# Power_Board_Testing_Interface.net
KiCad netlist of a schematic drawn in EAGLE
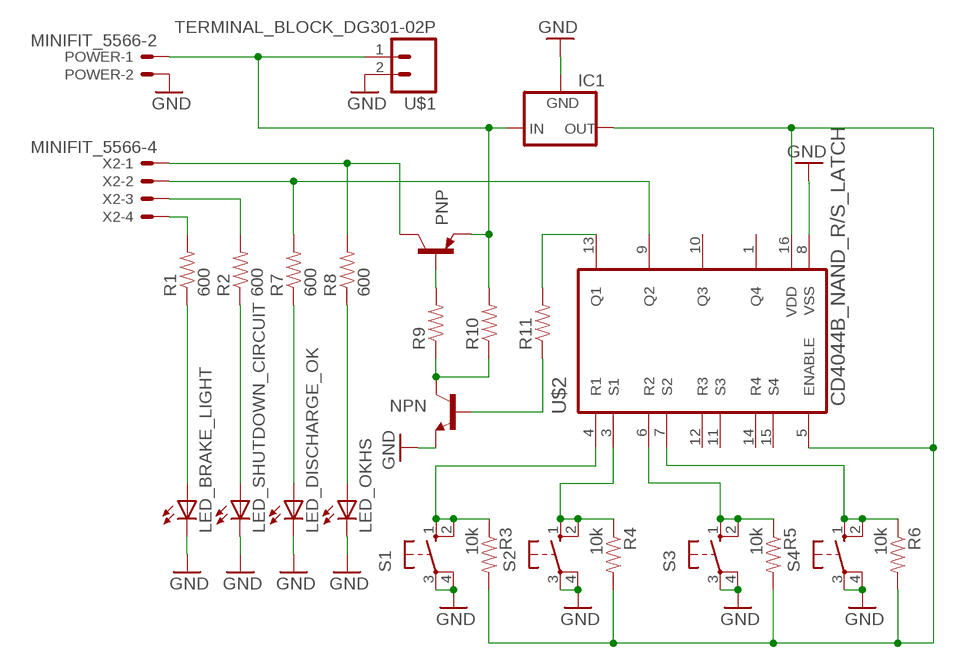
[diagram p0: schematic, sheet 1]

(export (version "E")
  (design (tool "Eeschema 10.0.6"))
  (components
    (comp (ref "IC1")
      (value "5V_REGULATOR_L7805SWITCHING")
      (footprint "eagle-import:TO-220")
      (libsource (lib "eagle-import") (part "5V_REGULATOR_L7805SWITCHING"))
    )
    (comp (ref "LED_BRAKE_LIGHT")
      (value "LED-5MM")
      (footprint "eagle-import:LED-5MM")
      (libsource (lib "eagle-import") (part "LED-5MM"))
    )
    (comp (ref "LED_DISCHARGE_OK")
      (value "LED-5MM")
      (footprint "eagle-import:LED-5MM")
      (libsource (lib "eagle-import") (part "LED-5MM"))
    )
    (comp (ref "LED_OKHS")
      (value "LED-5MM")
      (footprint "eagle-import:LED-5MM")
      (libsource (lib "eagle-import") (part "LED-5MM"))
    )
    (comp (ref "LED_SHUTDOWN_CIRCUIT")
      (value "LED-5MM")
      (footprint "eagle-import:LED-5MM")
      (libsource (lib "eagle-import") (part "LED-5MM"))
    )
    (comp (ref "NPN")
      (value "BJT_NPNTIP120")
      (footprint "eagle-import:TO-220")
      (libsource (lib "eagle-import") (part "BJT_NPNTIP120"))
    )
    (comp (ref "PNP")
      (value "BJT_PNP")
      (footprint "eagle-import:TO-220")
      (libsource (lib "eagle-import") (part "BJT_PNP"))
    )
    (comp (ref "POWER")
      (value "MINIFIT_5566-2")
      (footprint "eagle-import:MINIFIT_5566-2")
      (libsource (lib "eagle-import") (part "MINIFIT_5566-2"))
    )
    (comp (ref "R1")
      (value "600")
      (footprint "eagle-import:AXIAL-0.3EZ")
      (libsource (lib "eagle-import") (part "RESISTOREZ"))
    )
    (comp (ref "R2")
      (value "600")
      (footprint "eagle-import:AXIAL-0.3EZ")
      (libsource (lib "eagle-import") (part "RESISTOREZ"))
    )
    (comp (ref "R3")
      (value "10k")
      (footprint "eagle-import:AXIAL-0.3EZ")
      (libsource (lib "eagle-import") (part "RESISTOREZ"))
    )
    (comp (ref "R4")
      (value "10k")
      (footprint "eagle-import:AXIAL-0.3EZ")
      (libsource (lib "eagle-import") (part "RESISTOREZ"))
    )
    (comp (ref "R5")
      (value "10k")
      (footprint "eagle-import:AXIAL-0.3EZ")
      (libsource (lib "eagle-import") (part "RESISTOREZ"))
    )
    (comp (ref "R6")
      (value "10k")
      (footprint "eagle-import:AXIAL-0.3EZ")
      (libsource (lib "eagle-import") (part "RESISTOREZ"))
    )
    (comp (ref "R7")
      (value "600")
      (footprint "eagle-import:AXIAL-0.3EZ")
      (libsource (lib "eagle-import") (part "RESISTOREZ"))
    )
    (comp (ref "R8")
      (value "600")
      (footprint "eagle-import:AXIAL-0.3EZ")
      (libsource (lib "eagle-import") (part "RESISTOREZ"))
    )
    (comp (ref "R9")
      (value "RESISTOREZ")
      (footprint "eagle-import:AXIAL-0.3EZ")
      (libsource (lib "eagle-import") (part "RESISTOREZ"))
    )
    (comp (ref "R10")
      (value "RESISTOREZ")
      (footprint "eagle-import:AXIAL-0.3EZ")
      (libsource (lib "eagle-import") (part "RESISTOREZ"))
    )
    (comp (ref "R11")
      (value "RESISTOREZ")
      (footprint "eagle-import:AXIAL-0.3EZ")
      (libsource (lib "eagle-import") (part "RESISTOREZ"))
    )
    (comp (ref "S1")
      (value "BTN_10-XX")
      (footprint "eagle-import:B3F-10XX")
      (fields (field (name "MPN") "B3F-1000"))
      (libsource (lib "eagle-import") (part "BTN_10-XX"))
    )
    (comp (ref "S2")
      (value "BTN_10-XX")
      (footprint "eagle-import:B3F-10XX")
      (fields (field (name "MPN") "B3F-1000"))
      (libsource (lib "eagle-import") (part "BTN_10-XX"))
    )
    (comp (ref "S3")
      (value "BTN_10-XX")
      (footprint "eagle-import:B3F-10XX")
      (fields (field (name "MPN") "B3F-1000"))
      (libsource (lib "eagle-import") (part "BTN_10-XX"))
    )
    (comp (ref "S4")
      (value "BTN_10-XX")
      (footprint "eagle-import:B3F-10XX")
      (fields (field (name "MPN") "B3F-1000"))
      (libsource (lib "eagle-import") (part "BTN_10-XX"))
    )
    (comp (ref "U$1")
      (value "TERMINAL_BLOCK_DG301-02P")
      (footprint "eagle-import:DG301-02P")
      (libsource (lib "eagle-import") (part "TERMINAL_BLOCK_DG301-02P"))
    )
    (comp (ref "U$2")
      (value "CD4044B_NAND_R/S_LATCH")
      (footprint "eagle-import:DIL16")
      (libsource (lib "eagle-import") (part "CD4044B_NAND_R/S_LATCH"))
    )
    (comp (ref "X2")
      (value "MINIFIT_5566-4")
      (footprint "eagle-import:MINIFIT_5566-4")
      (libsource (lib "eagle-import") (part "MINIFIT_5566-4"))
    )
  )
  (nets
    (net (code "1") (name "/R3") (class "Default")
      (node (ref "U$2") (pin "12") (pinfunction "R3_12") (pintype "power_in"))
    )
    (net (code "2") (name "GND") (class "Default")
      (node (ref "IC1") (pin "2") (pinfunction "GND_2") (pintype "input"))
      (node (ref "LED_BRAKE_LIGHT") (pin "K") (pinfunction "C_K") (pintype "passive"))
      (node (ref "LED_DISCHARGE_OK") (pin "K") (pinfunction "C_K") (pintype "passive"))
      (node (ref "LED_OKHS") (pin "K") (pinfunction "C_K") (pintype "passive"))
      (node (ref "LED_SHUTDOWN_CIRCUIT") (pin "K") (pinfunction "C_K") (pintype "passive"))
      (node (ref "NPN") (pin "3") (pinfunction "EMITTER_3") (pintype "passive"))
      (node (ref "POWER") (pin "2") (pinfunction "S_2") (pintype "passive"))
      (node (ref "S1") (pin "3") (pinfunction "P_3") (pintype "passive"))
      (node (ref "S1") (pin "4") (pinfunction "P1_4") (pintype "passive"))
      (node (ref "S2") (pin "3") (pinfunction "P_3") (pintype "passive"))
      (node (ref "S2") (pin "4") (pinfunction "P1_4") (pintype "passive"))
      (node (ref "S3") (pin "3") (pinfunction "P_3") (pintype "passive"))
      (node (ref "S3") (pin "4") (pinfunction "P1_4") (pintype "passive"))
      (node (ref "S4") (pin "3") (pinfunction "P_3") (pintype "passive"))
      (node (ref "S4") (pin "4") (pinfunction "P1_4") (pintype "passive"))
      (node (ref "U$1") (pin "2") (pinfunction "2_2") (pintype "passive"))
      (node (ref "U$2") (pin "8") (pinfunction "VSS_8") (pintype "bidirectional"))
    )
    (net (code "3") (name "Net-(IC1-IN)") (class "Default")
      (node (ref "IC1") (pin "1") (pinfunction "IN_1") (pintype "input"))
      (node (ref "PNP") (pin "3") (pinfunction "E_3") (pintype "passive"))
      (node (ref "POWER") (pin "1") (pinfunction "S_1") (pintype "passive"))
      (node (ref "R10") (pin "P$2") (pinfunction "2_P$2") (pintype "passive"))
      (node (ref "U$1") (pin "1") (pinfunction "1_1") (pintype "passive"))
    )
    (net (code "4") (name "Net-(IC1-OUT)") (class "Default")
      (node (ref "IC1") (pin "3") (pinfunction "OUT_3") (pintype "output"))
      (node (ref "R3") (pin "P$2") (pinfunction "2_P$2") (pintype "passive"))
      (node (ref "R4") (pin "P$2") (pinfunction "2_P$2") (pintype "passive"))
      (node (ref "R5") (pin "P$2") (pinfunction "2_P$2") (pintype "passive"))
      (node (ref "R6") (pin "P$2") (pinfunction "2_P$2") (pintype "passive"))
      (node (ref "U$2") (pin "16") (pinfunction "VDD_16") (pintype "bidirectional"))
      (node (ref "U$2") (pin "5") (pinfunction "ENABLE_5") (pintype "passive"))
    )
    (net (code "5") (name "Net-(NPN-BASE)") (class "Default")
      (node (ref "NPN") (pin "1") (pinfunction "BASE_1") (pintype "passive"))
      (node (ref "R11") (pin "P$1") (pinfunction "1_P$1") (pintype "passive"))
    )
    (net (code "6") (name "Net-(NPN-COLLECTOR)") (class "Default")
      (node (ref "NPN") (pin "2") (pinfunction "COLLECTOR_2") (pintype "passive"))
      (node (ref "R10") (pin "P$1") (pinfunction "1_P$1") (pintype "passive"))
      (node (ref "R9") (pin "P$1") (pinfunction "1_P$1") (pintype "passive"))
    )
    (net (code "7") (name "Net-(PNP-B)") (class "Default")
      (node (ref "PNP") (pin "1") (pinfunction "B_1") (pintype "passive"))
      (node (ref "R9") (pin "P$2") (pinfunction "2_P$2") (pintype "passive"))
    )
    (net (code "8") (name "Net-(PNP-C)") (class "Default")
      (node (ref "PNP") (pin "2") (pinfunction "C_2") (pintype "passive"))
      (node (ref "R8") (pin "P$2") (pinfunction "2_P$2") (pintype "passive"))
      (node (ref "X2") (pin "1") (pinfunction "S_1") (pintype "passive"))
    )
    (net (code "9") (name "Net-(R1-1)") (class "Default")
      (node (ref "LED_BRAKE_LIGHT") (pin "A") (pinfunction "A_A") (pintype "passive"))
      (node (ref "R1") (pin "P$1") (pinfunction "1_P$1") (pintype "passive"))
    )
    (net (code "10") (name "Net-(R1-2)") (class "Default")
      (node (ref "R1") (pin "P$2") (pinfunction "2_P$2") (pintype "passive"))
      (node (ref "X2") (pin "4") (pinfunction "S_4") (pintype "passive"))
    )
    (net (code "11") (name "Net-(R2-1)") (class "Default")
      (node (ref "LED_SHUTDOWN_CIRCUIT") (pin "A") (pinfunction "A_A") (pintype "passive"))
      (node (ref "R2") (pin "P$1") (pinfunction "1_P$1") (pintype "passive"))
    )
    (net (code "12") (name "Net-(R2-2)") (class "Default")
      (node (ref "R2") (pin "P$2") (pinfunction "2_P$2") (pintype "passive"))
      (node (ref "X2") (pin "3") (pinfunction "S_3") (pintype "passive"))
    )
    (net (code "13") (name "Net-(R3-1)") (class "Default")
      (node (ref "R3") (pin "P$1") (pinfunction "1_P$1") (pintype "passive"))
      (node (ref "S1") (pin "1") (pinfunction "S_1") (pintype "passive"))
      (node (ref "S1") (pin "2") (pinfunction "S1_2") (pintype "passive"))
      (node (ref "U$2") (pin "4") (pinfunction "R1_4") (pintype "power_in"))
    )
    (net (code "14") (name "Net-(R4-1)") (class "Default")
      (node (ref "R4") (pin "P$1") (pinfunction "1_P$1") (pintype "passive"))
      (node (ref "S2") (pin "1") (pinfunction "S_1") (pintype "passive"))
      (node (ref "S2") (pin "2") (pinfunction "S1_2") (pintype "passive"))
      (node (ref "U$2") (pin "3") (pinfunction "S1_3") (pintype "input"))
    )
    (net (code "15") (name "Net-(R5-1)") (class "Default")
      (node (ref "R5") (pin "P$1") (pinfunction "1_P$1") (pintype "passive"))
      (node (ref "S3") (pin "1") (pinfunction "S_1") (pintype "passive"))
      (node (ref "S3") (pin "2") (pinfunction "S1_2") (pintype "passive"))
      (node (ref "U$2") (pin "6") (pinfunction "R2_6") (pintype "input"))
    )
    (net (code "16") (name "Net-(R6-1)") (class "Default")
      (node (ref "R6") (pin "P$1") (pinfunction "1_P$1") (pintype "passive"))
      (node (ref "S4") (pin "1") (pinfunction "S_1") (pintype "passive"))
      (node (ref "S4") (pin "2") (pinfunction "S1_2") (pintype "passive"))
      (node (ref "U$2") (pin "7") (pinfunction "S2_7") (pintype "input"))
    )
    (net (code "17") (name "Net-(R7-1)") (class "Default")
      (node (ref "LED_DISCHARGE_OK") (pin "A") (pinfunction "A_A") (pintype "passive"))
      (node (ref "R7") (pin "P$1") (pinfunction "1_P$1") (pintype "passive"))
    )
    (net (code "18") (name "Net-(R7-2)") (class "Default")
      (node (ref "R7") (pin "P$2") (pinfunction "2_P$2") (pintype "passive"))
      (node (ref "U$2") (pin "9") (pinfunction "Q2_9") (pintype "bidirectional"))
      (node (ref "X2") (pin "2") (pinfunction "S_2") (pintype "passive"))
    )
    (net (code "19") (name "Net-(R8-1)") (class "Default")
      (node (ref "LED_OKHS") (pin "A") (pinfunction "A_A") (pintype "passive"))
      (node (ref "R8") (pin "P$1") (pinfunction "1_P$1") (pintype "passive"))
    )
    (net (code "20") (name "Net-(R11-2)") (class "Default")
      (node (ref "R11") (pin "P$2") (pinfunction "2_P$2") (pintype "passive"))
      (node (ref "U$2") (pin "13") (pinfunction "Q1_13") (pintype "bidirectional"))
    )
    (net (code "21") (name "unconnected-(U$2-Q3-Pad10)") (class "Default")
      (node (ref "U$2") (pin "10") (pinfunction "Q3_10") (pintype "bidirectional"))
    )
    (net (code "22") (name "unconnected-(U$2-Q4-Pad1)") (class "Default")
      (node (ref "U$2") (pin "1") (pinfunction "Q4_1") (pintype "bidirectional"))
    )
    (net (code "23") (name "unconnected-(U$2-R4-Pad14)") (class "Default")
      (node (ref "U$2") (pin "14") (pinfunction "R4_14") (pintype "input"))
    )
    (net (code "24") (name "unconnected-(U$2-S3-Pad11)") (class "Default")
      (node (ref "U$2") (pin "11") (pinfunction "S3_11") (pintype "bidirectional"))
    )
    (net (code "25") (name "unconnected-(U$2-S4-Pad15)") (class "Default")
      (node (ref "U$2") (pin "15") (pinfunction "S4_15") (pintype "bidirectional"))
    )
  )
)
